# Power.net
KiCad netlist of a schematic drawn in Altium Designer
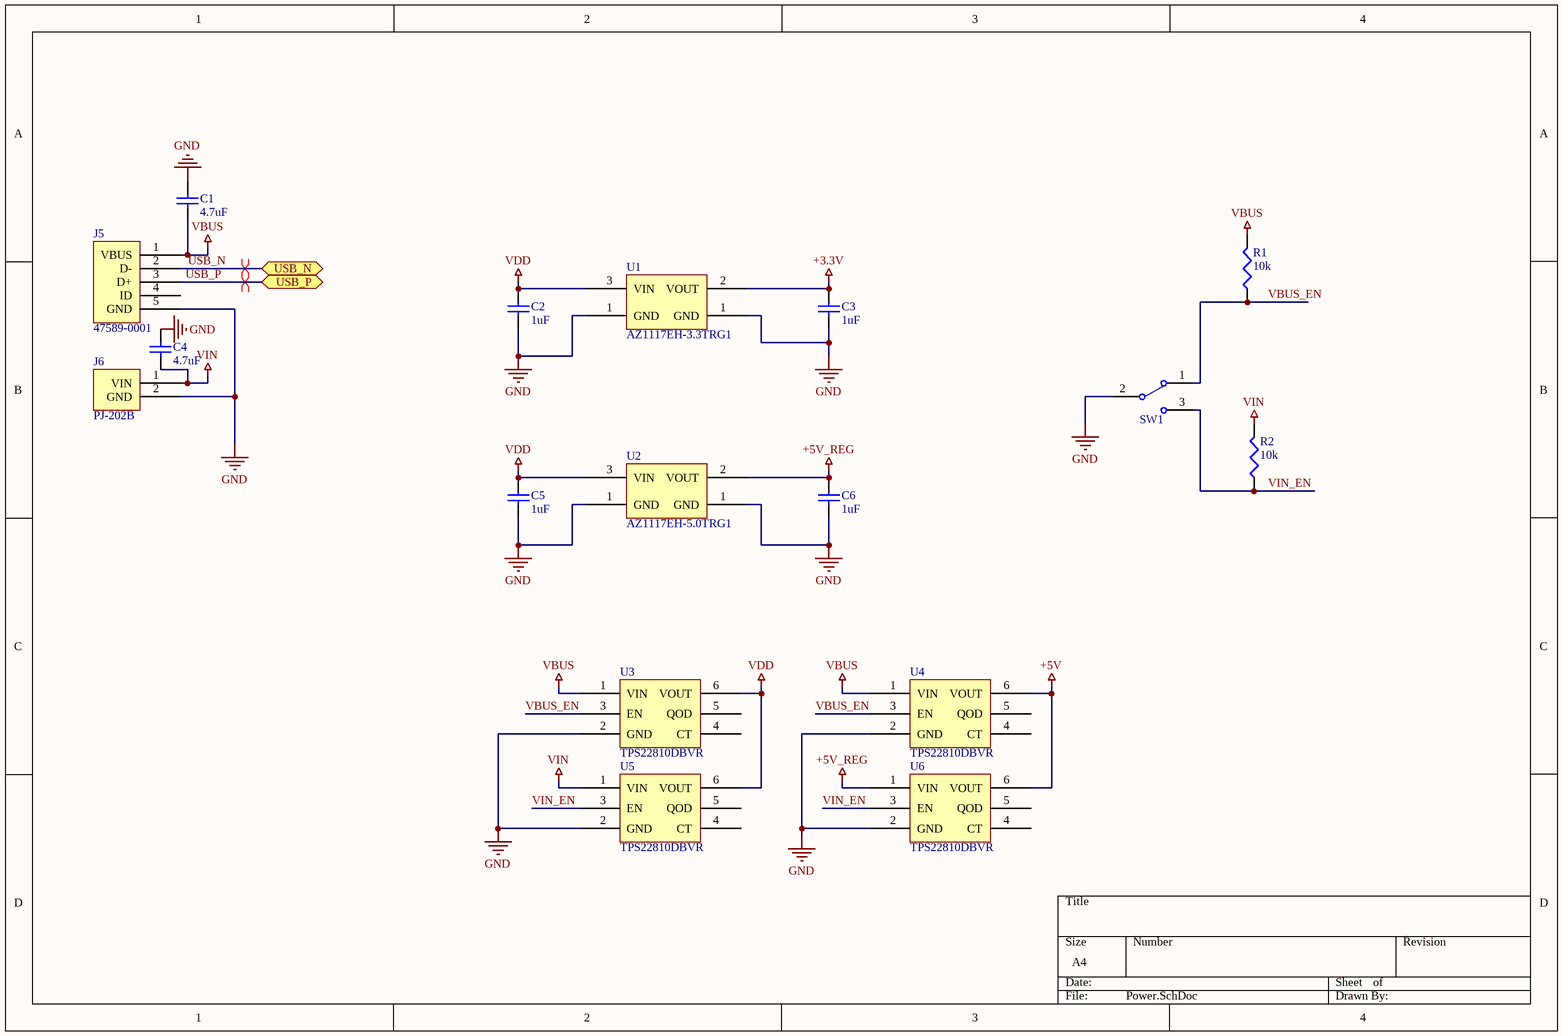
[diagram p0: Power.SchDoc]

(export (version "E")
  (design (tool "Eeschema 10.0.6"))
  (components
    (comp (ref "C1")
      (value "4.7uF")
      (footprint "CAPC2013X14N")
      (description "Cap Ceramic 4.7uF 25V X5R 10% SMD 0805 85C Embossed T/R")
      (fields
        (field (name "MANUFACTURER") "Samsung")
        (field (name "MANUFACTURER PART NUMBER") "CL21A475KAQNNNE")
      )
      (libsource (lib "Componentes") (part "CL21A475KAQNNNE"))
    )
    (comp (ref "C2")
      (value "1uF")
      (footprint "CAPC1608X09N_2")
      (description "Cap Ceramic 1uF 25V X5R 10% SMD 0603 85C Paper T/R")
      (fields
        (field (name "MANUFACTURER") "Samsung")
        (field (name "MANUFACTURER PART NUMBER") "CL10A105KA8NNNC")
      )
      (libsource (lib "Componentes") (part "CL10A105KA8NNNC"))
    )
    (comp (ref "C3")
      (value "1uF")
      (footprint "CAPC1608X09N_2")
      (description "Cap Ceramic 1uF 25V X5R 10% SMD 0603 85C Paper T/R")
      (fields
        (field (name "MANUFACTURER") "Samsung")
        (field (name "MANUFACTURER PART NUMBER") "CL10A105KA8NNNC")
      )
      (libsource (lib "Componentes") (part "CL10A105KA8NNNC"))
    )
    (comp (ref "C4")
      (value "4.7uF")
      (footprint "CAPC2013X14N")
      (description "Cap Ceramic 4.7uF 25V X5R 10% SMD 0805 85C Embossed T/R")
      (fields
        (field (name "MANUFACTURER") "Samsung")
        (field (name "MANUFACTURER PART NUMBER") "CL21A475KAQNNNE")
      )
      (libsource (lib "Componentes") (part "CL21A475KAQNNNE"))
    )
    (comp (ref "C5")
      (value "1uF")
      (footprint "CAPC1608X09N_2")
      (description "Cap Ceramic 1uF 25V X5R 10% SMD 0603 85C Paper T/R")
      (fields
        (field (name "MANUFACTURER") "Samsung")
        (field (name "MANUFACTURER PART NUMBER") "CL10A105KA8NNNC")
      )
      (libsource (lib "Componentes") (part "CL10A105KA8NNNC"))
    )
    (comp (ref "C6")
      (value "1uF")
      (footprint "CAPC1608X09N_2")
      (description "Cap Ceramic 1uF 25V X5R 10% SMD 0603 85C Paper T/R")
      (fields
        (field (name "MANUFACTURER") "Samsung")
        (field (name "MANUFACTURER PART NUMBER") "CL10A105KA8NNNC")
      )
      (libsource (lib "Componentes") (part "CL10A105KA8NNNC"))
    )
    (comp (ref "J5")
      (value "47589-0001")
      (footprint "USB")
      (description "MOLEX         47589-0001            MICRO USB, 2.0 TYPE AB, RECEPTACLE, SMT")
      (fields (field (name "MANUFACTURER") "Molex") (field (name "CHECKED") "False"))
      (libsource (lib "Componentes") (part "47589-0001"))
    )
    (comp (ref "J6")
      (value "PJ-202B")
      (footprint "POWER_JACK")
      (description "PJ-202 Series 2.5 x 6.5 mm 16 V Horizontal Power Jack w/ Kinked Pins")
      (fields (field (name "MANUFACTURER") "CUI"))
      (libsource (lib "Componentes") (part "PJ-202B"))
    )
    (comp (ref "R1")
      (value "10k")
      (footprint "RESC1608X05N")
      (description "RES SMD 10K OHM 0.5% 1/16W 0603")
      (fields
        (field (name "MANUFACTURER") "Susumu")
        (field (name "MANUFACTURER PART NUMBER") "RR0816P-103-D")
      )
      (libsource (lib "Componentes") (part "RR0816P-103-D"))
    )
    (comp (ref "R2")
      (value "10k")
      (footprint "RESC1608X05N")
      (description "RES SMD 10K OHM 0.5% 1/16W 0603")
      (fields
        (field (name "MANUFACTURER") "Susumu")
        (field (name "MANUFACTURER PART NUMBER") "RR0816P-103-D")
      )
      (libsource (lib "Componentes") (part "RR0816P-103-D"))
    )
    (comp (ref "SW1")
      (value "OS102011MS2QN1")
      (footprint "DIP5-SW")
      (fields (field (name "MANUFACTURER") "ITT C&K"))
      (libsource (lib "Componentes") (part "OS102011MS2QN1"))
    )
    (comp (ref "U1")
      (value "AZ1117EH-3.3TRG1")
      (footprint "SOT230P700X180-4N")
      (description "LDO Voltage Regulators LDO BJT HiCurr")
      (fields (field (name "MANUFACTURER") "Diodes"))
      (libsource (lib "Componentes") (part "AZ1117EH-3.3TRG1"))
    )
    (comp (ref "U2")
      (value "AZ1117EH-5.0TRG1")
      (footprint "SOT230P700X180-4N")
      (description "LDO Voltage Regulators LDO BJT HiCurr 1A 1.15V to 12V")
      (fields (field (name "MANUFACTURER") "Diodes"))
      (libsource (lib "Componentes") (part "AZ1117EH-5.0TRG1"))
    )
    (comp (ref "U3")
      (value "TPS22810DBVR")
      (footprint "SOT23127P600-8N-TPS22810DBVR")
      (libsource (lib "Componentes") (part "TPS22810DBVR"))
    )
    (comp (ref "U4")
      (value "TPS22810DBVR")
      (footprint "SOT23127P600-8N-TPS22810DBVR")
      (libsource (lib "Componentes") (part "TPS22810DBVR"))
    )
    (comp (ref "U5")
      (value "TPS22810DBVR")
      (footprint "SOT23127P600-8N-TPS22810DBVR")
      (libsource (lib "Componentes") (part "TPS22810DBVR"))
    )
    (comp (ref "U6")
      (value "TPS22810DBVR")
      (footprint "SOT23127P600-8N-TPS22810DBVR")
      (libsource (lib "Componentes") (part "TPS22810DBVR"))
    )
  )
  (nets
    (net (code "1") (name "+3.3V") (class "Default")
      (node (ref "C3") (pin "2") (pinfunction "2_2") (pintype "passive"))
      (node (ref "U1") (pin "2") (pinfunction "VOUT_2") (pintype "power_in"))
    )
    (net (code "2") (name "+5V") (class "Default")
      (node (ref "U4") (pin "6") (pinfunction "VOUT_6") (pintype "power_in"))
      (node (ref "U6") (pin "6") (pinfunction "VOUT_6") (pintype "power_in"))
    )
    (net (code "3") (name "+5V_REG") (class "Default")
      (node (ref "C6") (pin "2") (pinfunction "2_2") (pintype "passive"))
      (node (ref "U2") (pin "2") (pinfunction "VOUT_2") (pintype "power_in"))
      (node (ref "U6") (pin "1") (pinfunction "VIN_1") (pintype "power_in"))
    )
    (net (code "4") (name "/USB_N") (class "Default")
      (node (ref "J5") (pin "2") (pinfunction "D-_2") (pintype "power_in"))
    )
    (net (code "5") (name "/USB_P") (class "Default")
      (node (ref "J5") (pin "3") (pinfunction "D+_3") (pintype "power_in"))
    )
    (net (code "6") (name "/VBUS_EN") (class "Default")
      (node (ref "R1") (pin "1") (pinfunction "1_1") (pintype "passive"))
      (node (ref "SW1") (pin "1") (pinfunction "1_1") (pintype "power_in"))
      (node (ref "U3") (pin "3") (pinfunction "EN_3") (pintype "power_in"))
      (node (ref "U4") (pin "3") (pinfunction "EN_3") (pintype "power_in"))
    )
    (net (code "7") (name "/VIN_EN") (class "Default")
      (node (ref "R2") (pin "1") (pinfunction "1_1") (pintype "passive"))
      (node (ref "SW1") (pin "3") (pinfunction "3_3") (pintype "power_in"))
      (node (ref "U5") (pin "3") (pinfunction "EN_3") (pintype "power_in"))
      (node (ref "U6") (pin "3") (pinfunction "EN_3") (pintype "power_in"))
    )
    (net (code "8") (name "GND") (class "Default")
      (node (ref "C1") (pin "1") (pinfunction "1_1") (pintype "passive"))
      (node (ref "C2") (pin "1") (pinfunction "1_1") (pintype "passive"))
      (node (ref "C3") (pin "1") (pinfunction "1_1") (pintype "passive"))
      (node (ref "C4") (pin "1") (pinfunction "1_1") (pintype "passive"))
      (node (ref "C5") (pin "1") (pinfunction "1_1") (pintype "passive"))
      (node (ref "C6") (pin "1") (pinfunction "1_1") (pintype "passive"))
      (node (ref "J5") (pin "5") (pinfunction "GND_5") (pintype "power_in"))
      (node (ref "J6") (pin "2") (pinfunction "GND_2") (pintype "power_in"))
      (node (ref "J6") (pin "3") (pinfunction "GND_3") (pintype "power_in"))
      (node (ref "SW1") (pin "2") (pinfunction "2_2") (pintype "power_in"))
      (node (ref "U1") (pin "1") (pinfunction "GND_1") (pintype "power_in"))
      (node (ref "U2") (pin "1") (pinfunction "GND_1") (pintype "power_in"))
      (node (ref "U3") (pin "2") (pinfunction "GND_2") (pintype "power_in"))
      (node (ref "U4") (pin "2") (pinfunction "GND_2") (pintype "power_in"))
      (node (ref "U5") (pin "2") (pinfunction "GND_2") (pintype "power_in"))
      (node (ref "U6") (pin "2") (pinfunction "GND_2") (pintype "power_in"))
    )
    (net (code "9") (name "VBUS") (class "Default")
      (node (ref "C1") (pin "2") (pinfunction "2_2") (pintype "passive"))
      (node (ref "J5") (pin "1") (pinfunction "VBUS_1") (pintype "power_in"))
      (node (ref "R1") (pin "2") (pinfunction "2_2") (pintype "passive"))
      (node (ref "U3") (pin "1") (pinfunction "VIN_1") (pintype "power_in"))
      (node (ref "U4") (pin "1") (pinfunction "VIN_1") (pintype "power_in"))
    )
    (net (code "10") (name "VDD") (class "Default")
      (node (ref "C2") (pin "2") (pinfunction "2_2") (pintype "passive"))
      (node (ref "C5") (pin "2") (pinfunction "2_2") (pintype "passive"))
      (node (ref "U1") (pin "3") (pinfunction "VIN_3") (pintype "power_in"))
      (node (ref "U2") (pin "3") (pinfunction "VIN_3") (pintype "power_in"))
      (node (ref "U3") (pin "6") (pinfunction "VOUT_6") (pintype "power_in"))
      (node (ref "U5") (pin "6") (pinfunction "VOUT_6") (pintype "power_in"))
    )
    (net (code "11") (name "VIN") (class "Default")
      (node (ref "C4") (pin "2") (pinfunction "2_2") (pintype "passive"))
      (node (ref "J6") (pin "1") (pinfunction "VIN_1") (pintype "power_in"))
      (node (ref "R2") (pin "2") (pinfunction "2_2") (pintype "passive"))
      (node (ref "U5") (pin "1") (pinfunction "VIN_1") (pintype "power_in"))
    )
    (net (code "12") (name "unconnected-(J5-ID-Pad4)") (class "Default")
      (node (ref "J5") (pin "4") (pinfunction "ID_4") (pintype "power_in"))
    )
    (net (code "13") (name "unconnected-(U3-CT-Pad4)") (class "Default")
      (node (ref "U3") (pin "4") (pinfunction "CT_4") (pintype "power_in"))
    )
    (net (code "14") (name "unconnected-(U3-QOD-Pad5)") (class "Default")
      (node (ref "U3") (pin "5") (pinfunction "QOD_5") (pintype "power_in"))
    )
    (net (code "15") (name "unconnected-(U4-CT-Pad4)") (class "Default")
      (node (ref "U4") (pin "4") (pinfunction "CT_4") (pintype "power_in"))
    )
    (net (code "16") (name "unconnected-(U4-QOD-Pad5)") (class "Default")
      (node (ref "U4") (pin "5") (pinfunction "QOD_5") (pintype "power_in"))
    )
    (net (code "17") (name "unconnected-(U5-CT-Pad4)") (class "Default")
      (node (ref "U5") (pin "4") (pinfunction "CT_4") (pintype "power_in"))
    )
    (net (code "18") (name "unconnected-(U5-QOD-Pad5)") (class "Default")
      (node (ref "U5") (pin "5") (pinfunction "QOD_5") (pintype "power_in"))
    )
    (net (code "19") (name "unconnected-(U6-CT-Pad4)") (class "Default")
      (node (ref "U6") (pin "4") (pinfunction "CT_4") (pintype "power_in"))
    )
    (net (code "20") (name "unconnected-(U6-QOD-Pad5)") (class "Default")
      (node (ref "U6") (pin "5") (pinfunction "QOD_5") (pintype "power_in"))
    )
  )
)
